# ASCII_05_LMS7002M_RF1.net
KiCad netlist of a schematic drawn in Altium Designer
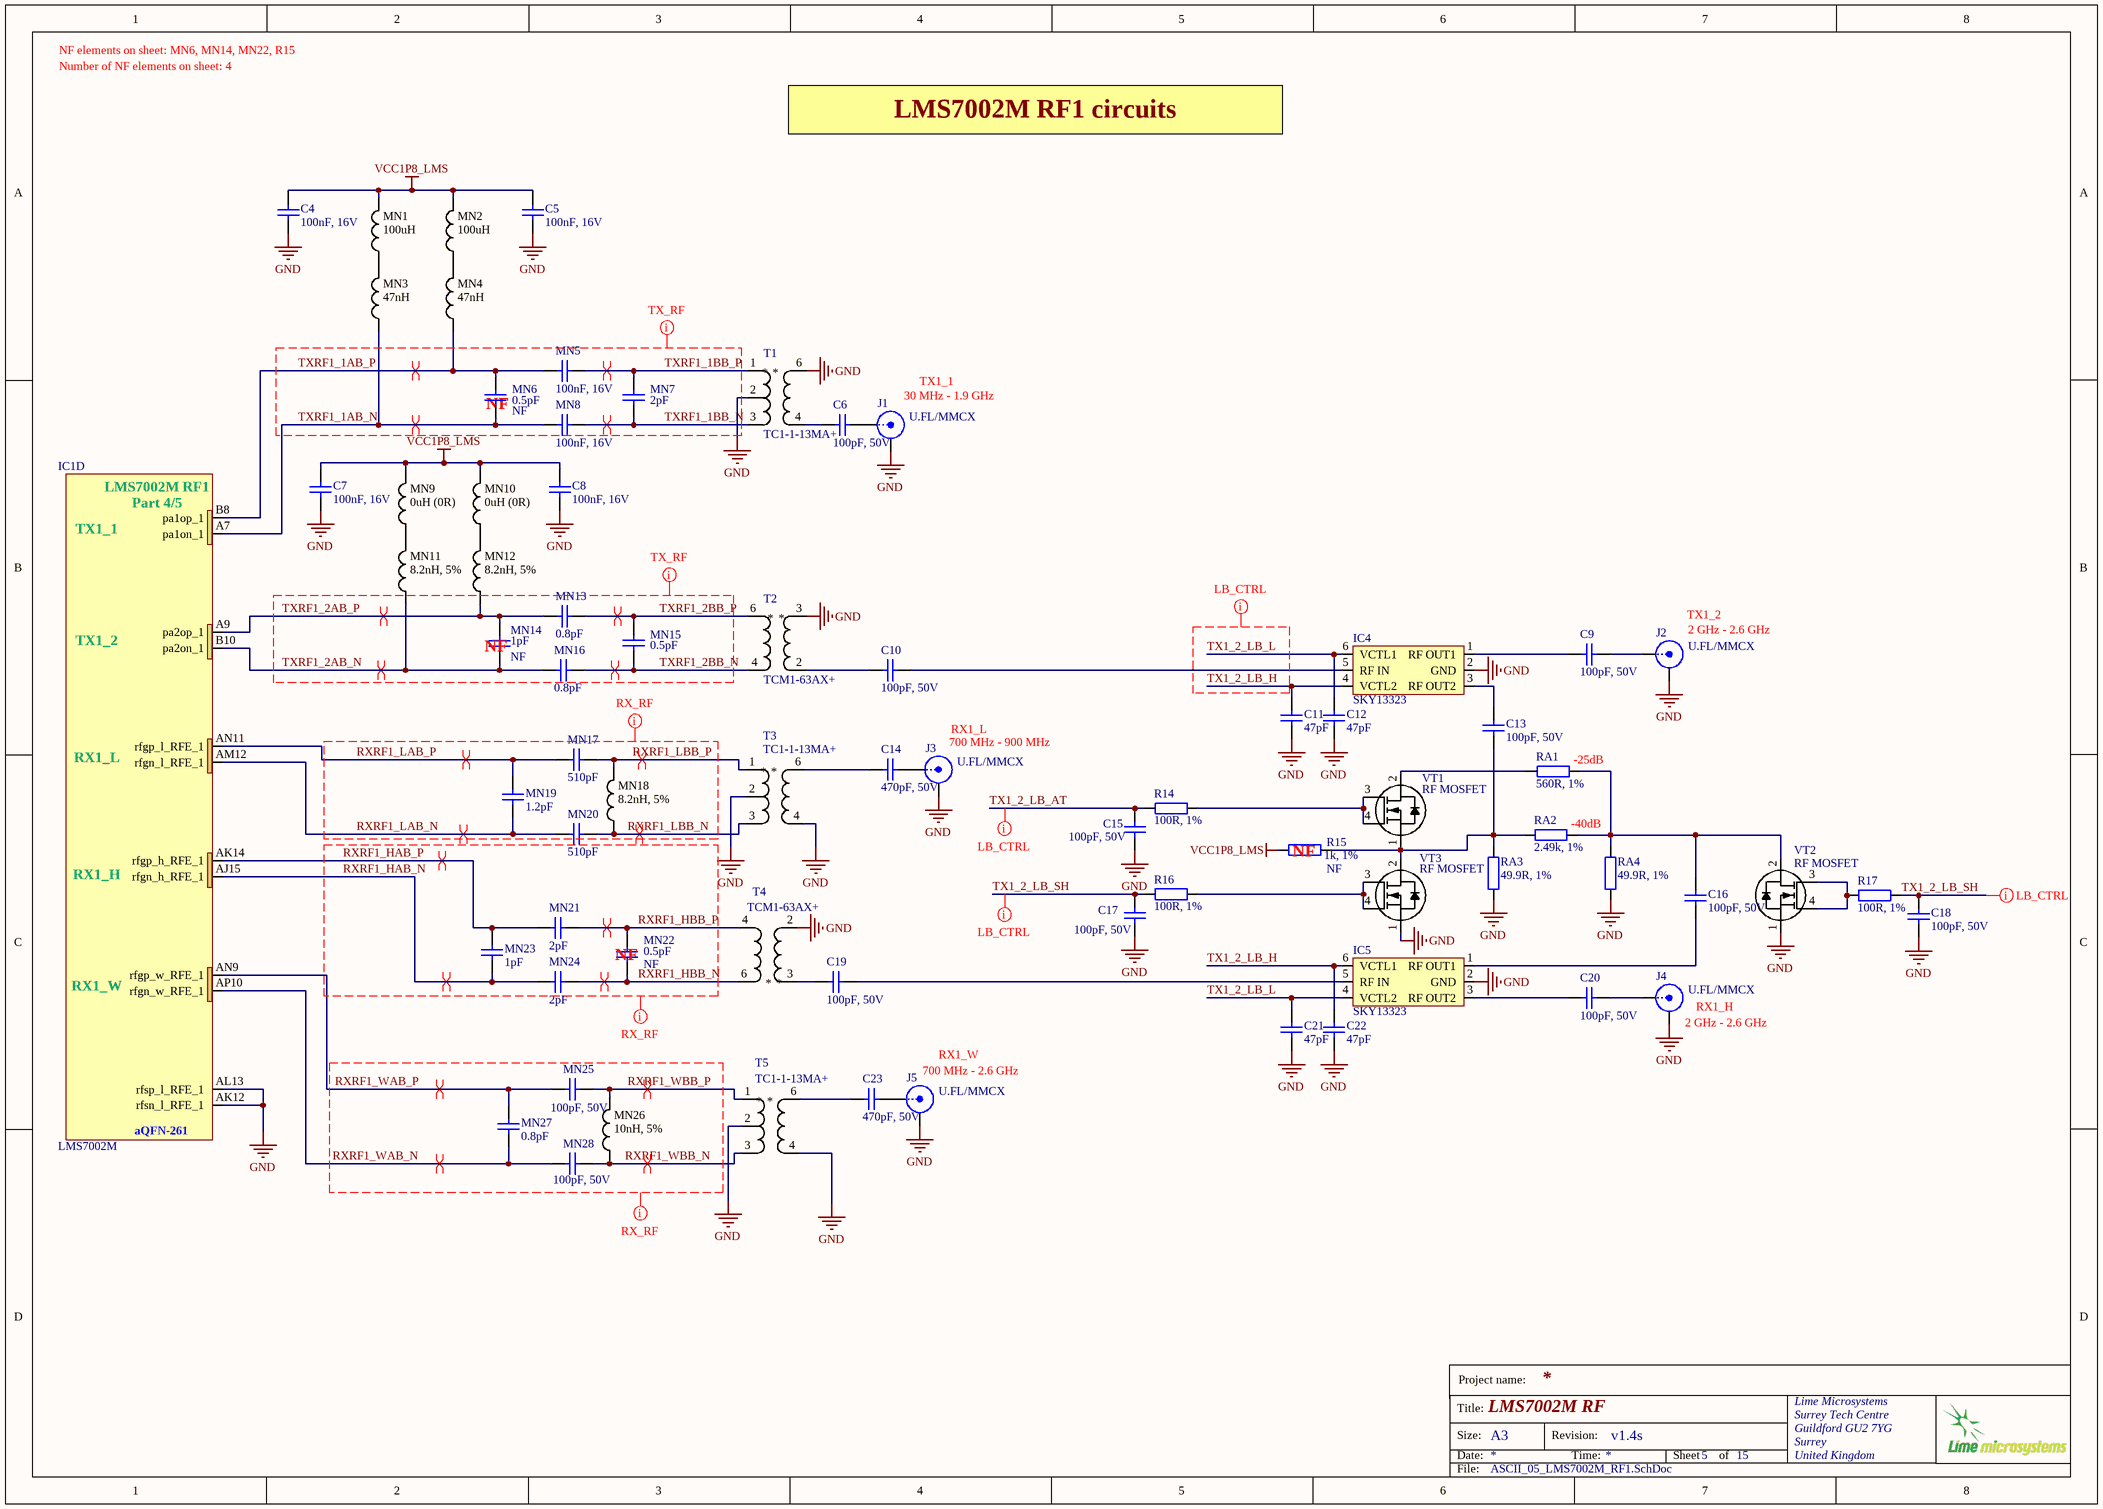
[diagram p0: ASCII_05_LMS7002M_RF1.SchDoc]

(export (version "E")
  (design (tool "Eeschema 10.0.6"))
  (components
    (comp (ref "C4")
      (value "100nF, 16V")
      (footprint "CAP0402")
      (fields
        (field (name "MANUFACTURER") "Murata Electronics")
        (field (name "TOLERANCE") "10 %")
        (field (name "MANUFACTURER PART NUMBER") "GRM155R71C104KA88D")
      )
      (libsource (lib "LimeMicroAltiumLib_schLib") (part "Cap_0402"))
    )
    (comp (ref "C5")
      (value "100nF, 16V")
      (footprint "CAP0402")
      (fields
        (field (name "MANUFACTURER") "Murata Electronics")
        (field (name "TOLERANCE") "10 %")
        (field (name "MANUFACTURER PART NUMBER") "GRM155R71C104KA88D")
      )
      (libsource (lib "LimeMicroAltiumLib_schLib") (part "Cap_0402"))
    )
    (comp (ref "C6")
      (value "100pF, 50V")
      (footprint "CAP0402")
      (fields (field (name "TOLERANCE") "±5%") (field (name "MANUFACTURER") "Yageo"))
      (libsource (lib "LimeMicroAltiumLib_schLib") (part "Cap_0402"))
    )
    (comp (ref "C7")
      (value "100nF, 16V")
      (footprint "CAP0402")
      (fields
        (field (name "MANUFACTURER") "Murata Electronics")
        (field (name "TOLERANCE") "10 %")
        (field (name "MANUFACTURER PART NUMBER") "GRM155R71C104KA88D")
      )
      (libsource (lib "LimeMicroAltiumLib_schLib") (part "Cap_0402"))
    )
    (comp (ref "C8")
      (value "100nF, 16V")
      (footprint "CAP0402")
      (fields
        (field (name "MANUFACTURER") "Murata Electronics")
        (field (name "TOLERANCE") "10 %")
        (field (name "MANUFACTURER PART NUMBER") "GRM155R71C104KA88D")
      )
      (libsource (lib "LimeMicroAltiumLib_schLib") (part "Cap_0402"))
    )
    (comp (ref "C9")
      (value "100pF, 50V")
      (footprint "CAP0402")
      (fields (field (name "TOLERANCE") "±5%") (field (name "MANUFACTURER") "Yageo"))
      (libsource (lib "LimeMicroAltiumLib_schLib") (part "Cap_0402"))
    )
    (comp (ref "C10")
      (value "100pF, 50V")
      (footprint "CAP0402")
      (fields (field (name "TOLERANCE") "±5%") (field (name "MANUFACTURER") "Yageo"))
      (libsource (lib "LimeMicroAltiumLib_schLib") (part "Cap_0402"))
    )
    (comp (ref "C11")
      (value "47pF")
      (footprint "CAP0402")
      (fields (field (name "TOLERANCE") "±1%") (field (name "MANUFACTURER") "TDK Corporation"))
      (libsource (lib "LimeMicroAltiumLib_schLib") (part "Cap_0402"))
    )
    (comp (ref "C12")
      (value "47pF")
      (footprint "CAP0402")
      (fields (field (name "TOLERANCE") "±1%") (field (name "MANUFACTURER") "TDK Corporation"))
      (libsource (lib "LimeMicroAltiumLib_schLib") (part "Cap_0402"))
    )
    (comp (ref "C13")
      (value "100pF, 50V")
      (footprint "CAP0402")
      (fields (field (name "TOLERANCE") "±5%") (field (name "MANUFACTURER") "Yageo"))
      (libsource (lib "LimeMicroAltiumLib_schLib") (part "Cap_0402"))
    )
    (comp (ref "C14")
      (value "470pF, 50V")
      (footprint "CAP0402")
      (fields
        (field (name "MANUFACTURER PART NUMBER") "C1005C0G1H471J050BA")
        (field (name "TOLERANCE") "±5%")
        (field (name "MANUFACTURER") "TDK Corporation")
      )
      (libsource (lib "LimeMicroAltiumLib_schLib") (part "Cap_0402"))
    )
    (comp (ref "C15")
      (value "100pF, 50V")
      (footprint "CAP0402")
      (fields (field (name "TOLERANCE") "±5%") (field (name "MANUFACTURER") "Yageo"))
      (libsource (lib "LimeMicroAltiumLib_schLib") (part "Cap_0402"))
    )
    (comp (ref "C16")
      (value "100pF, 50V")
      (footprint "CAP0402")
      (fields (field (name "TOLERANCE") "±5%") (field (name "MANUFACTURER") "Yageo"))
      (libsource (lib "LimeMicroAltiumLib_schLib") (part "Cap_0402"))
    )
    (comp (ref "C17")
      (value "100pF, 50V")
      (footprint "CAP0402")
      (fields (field (name "TOLERANCE") "±5%") (field (name "MANUFACTURER") "Yageo"))
      (libsource (lib "LimeMicroAltiumLib_schLib") (part "Cap_0402"))
    )
    (comp (ref "C18")
      (value "100pF, 50V")
      (footprint "CAP0402")
      (fields (field (name "TOLERANCE") "±5%") (field (name "MANUFACTURER") "Yageo"))
      (libsource (lib "LimeMicroAltiumLib_schLib") (part "Cap_0402"))
    )
    (comp (ref "C19")
      (value "100pF, 50V")
      (footprint "CAP0402")
      (fields (field (name "TOLERANCE") "±5%") (field (name "MANUFACTURER") "Yageo"))
      (libsource (lib "LimeMicroAltiumLib_schLib") (part "Cap_0402"))
    )
    (comp (ref "C20")
      (value "100pF, 50V")
      (footprint "CAP0402")
      (fields (field (name "TOLERANCE") "±5%") (field (name "MANUFACTURER") "Yageo"))
      (libsource (lib "LimeMicroAltiumLib_schLib") (part "Cap_0402"))
    )
    (comp (ref "C21")
      (value "47pF")
      (footprint "CAP0402")
      (fields (field (name "TOLERANCE") "±1%") (field (name "MANUFACTURER") "TDK Corporation"))
      (libsource (lib "LimeMicroAltiumLib_schLib") (part "Cap_0402"))
    )
    (comp (ref "C22")
      (value "47pF")
      (footprint "CAP0402")
      (fields (field (name "TOLERANCE") "±1%") (field (name "MANUFACTURER") "TDK Corporation"))
      (libsource (lib "LimeMicroAltiumLib_schLib") (part "Cap_0402"))
    )
    (comp (ref "C23")
      (value "470pF, 50V")
      (footprint "CAP0402")
      (fields
        (field (name "MANUFACTURER PART NUMBER") "C1005C0G1H471J050BA")
        (field (name "TOLERANCE") "±5%")
        (field (name "MANUFACTURER") "TDK Corporation")
      )
      (libsource (lib "LimeMicroAltiumLib_schLib") (part "Cap_0402"))
    )
    (comp (ref "IC1")
      (value "LMS7002M")
      (footprint "LMS7002M_v3")
      (fields (field (name "MANUFACTURER") "Lime Microsystems"))
      (libsource (lib "LimeMicroAltiumLib_schLib") (part "LMS7002M"))
    )
    (comp (ref "IC4")
      (value "SKY13323")
      (footprint "SKY13323-378LF")
      (description "SKY13323-378LF: 0.1-3.0 GHz GaAs SPDT Switch")
      (fields (field (name "MANUFACTURER") "Skyworks Solutions Inc."))
      (libsource (lib "LimeMicroAltiumLib_schLib") (part "SKY13323"))
    )
    (comp (ref "IC5")
      (value "SKY13323")
      (footprint "SKY13323-378LF")
      (description "SKY13323-378LF: 0.1-3.0 GHz GaAs SPDT Switch")
      (fields (field (name "MANUFACTURER") "Skyworks Solutions Inc."))
      (libsource (lib "LimeMicroAltiumLib_schLib") (part "SKY13323"))
    )
    (comp (ref "J1")
      (value "U.FL/MMCX")
      (footprint "MMCX_UFL_conn_u")
      (description "CONN UMC RCPT STR 50 OHM SMD")
      (fields (field (name "MANUFACTURER") "Molex, LLC"))
      (libsource (lib "LimeMicroAltiumLib_schLib") (part "RF_IF_connector"))
    )
    (comp (ref "J2")
      (value "U.FL/MMCX")
      (footprint "MMCX_UFL_conn_u")
      (description "CONN UMC RCPT STR 50 OHM SMD")
      (fields (field (name "MANUFACTURER") "Molex, LLC"))
      (libsource (lib "LimeMicroAltiumLib_schLib") (part "RF_IF_connector"))
    )
    (comp (ref "J3")
      (value "U.FL/MMCX")
      (footprint "MMCX_UFL_conn_u")
      (description "CONN UMC RCPT STR 50 OHM SMD")
      (fields (field (name "MANUFACTURER") "Molex, LLC"))
      (libsource (lib "LimeMicroAltiumLib_schLib") (part "RF_IF_connector"))
    )
    (comp (ref "J4")
      (value "U.FL/MMCX")
      (footprint "MMCX_UFL_conn_u")
      (description "CONN UMC RCPT STR 50 OHM SMD")
      (fields (field (name "MANUFACTURER") "Molex, LLC"))
      (libsource (lib "LimeMicroAltiumLib_schLib") (part "RF_IF_connector"))
    )
    (comp (ref "J5")
      (value "U.FL/MMCX")
      (footprint "MMCX_UFL_conn_u")
      (description "CONN UMC RCPT STR 50 OHM SMD")
      (fields (field (name "MANUFACTURER") "Molex, LLC"))
      (libsource (lib "LimeMicroAltiumLib_schLib") (part "RF_IF_connector"))
    )
    (comp (ref "MN1")
      (value "100uH")
      (footprint "RES0805")
      (fields
        (field (name "TOLERANCE") "±10%")
        (field (name "MANUFACTURER") "TDK Corporation")
        (field (name "MANUFACTURER PART NUMBER") "MLF2012C101KT000")
      )
      (libsource (lib "LimeMicroAltiumLib_schLib") (part "Inductor_0603"))
    )
    (comp (ref "MN2")
      (value "100uH")
      (footprint "RES0805")
      (fields
        (field (name "TOLERANCE") "±10%")
        (field (name "MANUFACTURER") "TDK Corporation")
        (field (name "MANUFACTURER PART NUMBER") "MLF2012C101KT000")
      )
      (libsource (lib "LimeMicroAltiumLib_schLib") (part "Inductor_0603"))
    )
    (comp (ref "MN3")
      (value "47nH")
      (footprint "RES0402")
      (fields
        (field (name "MANUFACTURER") "COILCRAFT")
        (field (name "MANUFACTURER PART NUMBER") "0402HP-47NXJLU")
      )
      (libsource (lib "LimeMicroAltiumLib_schLib") (part "Inductor_0603"))
    )
    (comp (ref "MN4")
      (value "47nH")
      (footprint "RES0402")
      (fields
        (field (name "MANUFACTURER") "COILCRAFT")
        (field (name "MANUFACTURER PART NUMBER") "0402HP-47NXJLU")
      )
      (libsource (lib "LimeMicroAltiumLib_schLib") (part "Inductor_0603"))
    )
    (comp (ref "MN5")
      (value "100nF, 16V")
      (footprint "CAP0402")
      (fields
        (field (name "MANUFACTURER") "Murata Electronics")
        (field (name "TOLERANCE") "10 %")
        (field (name "MANUFACTURER PART NUMBER") "GRM155R71C104KA88D")
      )
      (libsource (lib "LimeMicroAltiumLib_schLib") (part "Cap_0402"))
    )
    (comp (ref "MN6")
      (value "0.5pF")
      (footprint "CAP0402")
      (fields
        (field (name "ASSEMBLY INFO") "NF")
        (field (name "TOLERANCE") "±0.25pF")
        (field (name "MANUFACTURER") "Yageo")
      )
      (libsource (lib "LimeMicroAltiumLib_schLib") (part "Cap_0402"))
    )
    (comp (ref "MN7")
      (value "2pF")
      (footprint "CAP0402")
      (fields (field (name "MANUFACTURER PART NUMBER") "04025U2R0BAT2A") (field (name "MANUFACTURER") "AVX"))
      (libsource (lib "LimeMicroAltiumLib_schLib") (part "Cap_0402"))
    )
    (comp (ref "MN8")
      (value "100nF, 16V")
      (footprint "CAP0402")
      (fields
        (field (name "MANUFACTURER") "Murata Electronics")
        (field (name "TOLERANCE") "10 %")
        (field (name "MANUFACTURER PART NUMBER") "GRM155R71C104KA88D")
      )
      (libsource (lib "LimeMicroAltiumLib_schLib") (part "Cap_0402"))
    )
    (comp (ref "MN9")
      (value "0uH (0R)")
      (footprint "RES0805")
      (fields (field (name "MANUFACTURER") "BOURNS"))
      (libsource (lib "LimeMicroAltiumLib_schLib") (part "Inductor_0603"))
    )
    (comp (ref "MN10")
      (value "0uH (0R)")
      (footprint "RES0805")
      (fields (field (name "MANUFACTURER") "BOURNS"))
      (libsource (lib "LimeMicroAltiumLib_schLib") (part "Inductor_0603"))
    )
    (comp (ref "MN11")
      (value "8.2nH, 5%")
      (footprint "RES0402")
      (fields (field (name "MANUFACTURER") "COILCRAFT"))
      (libsource (lib "LimeMicroAltiumLib_schLib") (part "Inductor_0603"))
    )
    (comp (ref "MN12")
      (value "8.2nH, 5%")
      (footprint "RES0402")
      (fields (field (name "MANUFACTURER") "COILCRAFT"))
      (libsource (lib "LimeMicroAltiumLib_schLib") (part "Inductor_0603"))
    )
    (comp (ref "MN13")
      (value "0.8pF")
      (footprint "CAP0402")
      (fields
        (field (name "TOLERANCE") "±0.1pF")
        (field (name "MANUFACTURER") "Murata Electronics North America")
        (field (name "MANUFACTURER PART NUMBER") "GRM1555C1HR80BA01D")
      )
      (libsource (lib "LimeMicroAltiumLib_schLib") (part "Cap_0402"))
    )
    (comp (ref "MN14")
      (value "1pF")
      (footprint "CAP0402")
      (fields
        (field (name "ASSEMBLY INFO") "NF")
        (field (name "MANUFACTURER") "TDK Corporation")
        (field (name "TOLERANCE") "±0.1pF")
      )
      (libsource (lib "LimeMicroAltiumLib_schLib") (part "Cap_0402"))
    )
    (comp (ref "MN15")
      (value "0.5pF")
      (footprint "CAP0402")
      (fields (field (name "TOLERANCE") "±0.25pF") (field (name "MANUFACTURER") "Yageo"))
      (libsource (lib "LimeMicroAltiumLib_schLib") (part "Cap_0402"))
    )
    (comp (ref "MN16")
      (value "0.8pF")
      (footprint "CAP0402")
      (fields
        (field (name "TOLERANCE") "±0.1pF")
        (field (name "MANUFACTURER") "Murata Electronics North America")
        (field (name "MANUFACTURER PART NUMBER") "GRM1555C1HR80BA01D")
      )
      (libsource (lib "LimeMicroAltiumLib_schLib") (part "Cap_0402"))
    )
    (comp (ref "MN17")
      (value "510pF")
      (footprint "CAP0402")
      (fields
        (field (name "TOLERANCE") "±5%")
        (field (name "MANUFACTURER") "Murata Electronics North America")
        (field (name "MANUFACTURER PART NUMBER") "GRM1555C1H511JA01D")
      )
      (libsource (lib "LimeMicroAltiumLib_schLib") (part "Cap_0402"))
    )
    (comp (ref "MN18")
      (value "8.2nH, 5%")
      (footprint "RES0402")
      (fields (field (name "MANUFACTURER") "COILCRAFT"))
      (libsource (lib "LimeMicroAltiumLib_schLib") (part "Inductor_0603"))
    )
    (comp (ref "MN19")
      (value "1.2pF")
      (footprint "CAP0402")
      (fields
        (field (name "MANUFACTURER") "Murata Electronics North America")
        (field (name "MANUFACTURER PART NUMBER") "GRM1555C1H1R2CA01D")
        (field (name "TOLERANCE") "±0.25pF")
      )
      (libsource (lib "LimeMicroAltiumLib_schLib") (part "Cap_0402"))
    )
    (comp (ref "MN20")
      (value "510pF")
      (footprint "CAP0402")
      (fields
        (field (name "TOLERANCE") "±5%")
        (field (name "MANUFACTURER") "Murata Electronics North America")
        (field (name "MANUFACTURER PART NUMBER") "GRM1555C1H511JA01D")
      )
      (libsource (lib "LimeMicroAltiumLib_schLib") (part "Cap_0402"))
    )
    (comp (ref "MN21")
      (value "2pF")
      (footprint "CAP0402")
      (fields (field (name "MANUFACTURER PART NUMBER") "04025U2R0BAT2A") (field (name "MANUFACTURER") "AVX"))
      (libsource (lib "LimeMicroAltiumLib_schLib") (part "Cap_0402"))
    )
    (comp (ref "MN22")
      (value "0.5pF")
      (footprint "CAP0402")
      (fields
        (field (name "ASSEMBLY INFO") "NF")
        (field (name "TOLERANCE") "±0.25pF")
        (field (name "MANUFACTURER") "Yageo")
      )
      (libsource (lib "LimeMicroAltiumLib_schLib") (part "Cap_0402"))
    )
    (comp (ref "MN23")
      (value "1pF")
      (footprint "CAP0402")
      (fields (field (name "MANUFACTURER") "TDK Corporation") (field (name "TOLERANCE") "±0.1pF"))
      (libsource (lib "LimeMicroAltiumLib_schLib") (part "Cap_0402"))
    )
    (comp (ref "MN24")
      (value "2pF")
      (footprint "CAP0402")
      (fields (field (name "MANUFACTURER PART NUMBER") "04025U2R0BAT2A") (field (name "MANUFACTURER") "AVX"))
      (libsource (lib "LimeMicroAltiumLib_schLib") (part "Cap_0402"))
    )
    (comp (ref "MN25")
      (value "100pF, 50V")
      (footprint "CAP0402")
      (fields (field (name "TOLERANCE") "±5%") (field (name "MANUFACTURER") "Yageo"))
      (libsource (lib "LimeMicroAltiumLib_schLib") (part "Cap_0402"))
    )
    (comp (ref "MN26")
      (value "10nH, 5%")
      (footprint "RES0402")
      (fields (field (name "MANUFACTURER") "COILCRAFT"))
      (libsource (lib "LimeMicroAltiumLib_schLib") (part "Inductor_0603"))
    )
    (comp (ref "MN27")
      (value "0.8pF")
      (footprint "CAP0402")
      (fields
        (field (name "TOLERANCE") "±0.1pF")
        (field (name "MANUFACTURER") "Murata Electronics North America")
        (field (name "MANUFACTURER PART NUMBER") "GRM1555C1HR80BA01D")
      )
      (libsource (lib "LimeMicroAltiumLib_schLib") (part "Cap_0402"))
    )
    (comp (ref "MN28")
      (value "100pF, 50V")
      (footprint "CAP0402")
      (fields (field (name "TOLERANCE") "±5%") (field (name "MANUFACTURER") "Yageo"))
      (libsource (lib "LimeMicroAltiumLib_schLib") (part "Cap_0402"))
    )
    (comp (ref "R14")
      (value "100R, 1%")
      (footprint "RES0402")
      (fields (field (name "TOLERANCE") "±1%") (field (name "MANUFACTURER") "Stackpole Electronics Inc."))
      (libsource (lib "LimeFPGAboard_schLib") (part "Res_0402"))
    )
    (comp (ref "R15")
      (value "1k, 1%")
      (footprint "RES0402")
      (fields
        (field (name "ASSEMBLY INFO") "NF")
        (field (name "MANUFACTURER") "Stackpole Electronics Inc")
        (field (name "TOLERANCE") "±1%")
      )
      (libsource (lib "LimeMicroAltiumLib_schLib") (part "Res_0402"))
    )
    (comp (ref "R16")
      (value "100R, 1%")
      (footprint "RES0402")
      (fields (field (name "TOLERANCE") "±1%") (field (name "MANUFACTURER") "Stackpole Electronics Inc."))
      (libsource (lib "LimeFPGAboard_schLib") (part "Res_0402"))
    )
    (comp (ref "R17")
      (value "100R, 1%")
      (footprint "RES0402")
      (fields (field (name "TOLERANCE") "±1%") (field (name "MANUFACTURER") "Stackpole Electronics Inc."))
      (libsource (lib "LimeFPGAboard_schLib") (part "Res_0402"))
    )
    (comp (ref "RA1")
      (value "560R, 1%")
      (footprint "RES0402")
      (fields
        (field (name "MANUFACTURER PART NUMBER") "CRCW0402560RFKED")
        (field (name "TOLERANCE") "±1%")
        (field (name "MANUFACTURER") "Vishay Dale")
      )
      (libsource (lib "LimeMicroAltiumLib_schLib") (part "Res_0402"))
    )
    (comp (ref "RA2")
      (value "2.49k, 1%")
      (footprint "RES0402")
      (fields
        (field (name "TOLERANCE") "±1%")
        (field (name "MANUFACTURER PART NUMBER") "RC0402FR-072K49L")
        (field (name "MANUFACTURER") "Yageo")
      )
      (libsource (lib "LimeMicroAltiumLib_schLib") (part "Res_0402"))
    )
    (comp (ref "RA3")
      (value "49.9R, 1%")
      (footprint "RES0402")
      (fields
        (field (name "TOLERANCE") "±1%")
        (field (name "MANUFACTURER") "Samsung Electro-Mechanics America, Inc.")
        (field (name "MANUFACTURER PART NUMBER") "RC1005F49R9CS")
      )
      (libsource (lib "LimeMicroAltiumLib_schLib") (part "Res_0402"))
    )
    (comp (ref "RA4")
      (value "49.9R, 1%")
      (footprint "RES0402")
      (fields
        (field (name "TOLERANCE") "±1%")
        (field (name "MANUFACTURER") "Samsung Electro-Mechanics America, Inc.")
        (field (name "MANUFACTURER PART NUMBER") "RC1005F49R9CS")
      )
      (libsource (lib "LimeMicroAltiumLib_schLib") (part "Res_0402"))
    )
    (comp (ref "T1")
      (value "TC1-1-13MA+")
      (footprint "TC1-1-13MA+_v2")
      (fields (field (name "MANUFACTURER") "Mini-Circuits"))
      (libsource (lib "LimeMicroAltiumLib_schLib") (part "Balun"))
    )
    (comp (ref "T2")
      (value "TCM1-63AX+")
      (footprint "TCM1-63AX+_v2")
      (fields (field (name "MANUFACTURER") "Mini-circuits"))
      (libsource (lib "LimeMicroAltiumLib_schLib") (part "Balun_v2"))
    )
    (comp (ref "T3")
      (value "TC1-1-13MA+")
      (footprint "TC1-1-13MA+_v2")
      (fields (field (name "MANUFACTURER") "Mini-Circuits"))
      (libsource (lib "LimeMicroAltiumLib_schLib") (part "Balun"))
    )
    (comp (ref "T4")
      (value "TCM1-63AX+")
      (footprint "TCM1-63AX+_v2")
      (fields (field (name "MANUFACTURER") "Mini-circuits"))
      (libsource (lib "") (part "Balun_v2_1"))
    )
    (comp (ref "T5")
      (value "TC1-1-13MA+")
      (footprint "TC1-1-13MA+_v2")
      (fields (field (name "MANUFACTURER") "Mini-Circuits"))
      (libsource (lib "LimeMicroAltiumLib_schLib") (part "Balun"))
    )
    (comp (ref "VT1")
      (value "RF MOSFET")
      (footprint "BF1105R_SOT143R4")
      (fields (field (name "MANUFACTURER") "NXP Semiconductors"))
      (libsource (lib "LimeMicroAltiumLib_schLib") (part "BF1105R,215"))
    )
    (comp (ref "VT2")
      (value "RF MOSFET")
      (footprint "BF1105R_SOT143R4")
      (fields (field (name "MANUFACTURER") "NXP Semiconductors"))
      (libsource (lib "LimeMicroAltiumLib_schLib") (part "BF1105R,215"))
    )
    (comp (ref "VT3")
      (value "RF MOSFET")
      (footprint "BF1105R_SOT143R4")
      (fields (field (name "MANUFACTURER") "NXP Semiconductors"))
      (libsource (lib "LimeMicroAltiumLib_schLib") (part "BF1105R,215"))
    )
  )
  (nets
    (net (code "1") (name "/RXRF1_HAB_N") (class "Default")
      (node (ref "IC1") (pin "AJ15") (pinfunction "rfgn_h_RFE_1_AJ15") (pintype "passive"))
      (node (ref "MN23") (pin "1") (pinfunction "1_1") (pintype "passive"))
      (node (ref "MN24") (pin "2") (pinfunction "2_2") (pintype "passive"))
    )
    (net (code "2") (name "/RXRF1_HAB_P") (class "Default")
      (node (ref "IC1") (pin "AK14") (pinfunction "rfgp_h_RFE_1_AK14") (pintype "passive"))
      (node (ref "MN21") (pin "2") (pinfunction "2_2") (pintype "passive"))
      (node (ref "MN23") (pin "2") (pinfunction "2_2") (pintype "passive"))
    )
    (net (code "3") (name "/RXRF1_HBB_N") (class "Default")
      (node (ref "MN22") (pin "1") (pinfunction "1_1") (pintype "passive"))
      (node (ref "MN24") (pin "1") (pinfunction "1_1") (pintype "passive"))
      (node (ref "T4") (pin "6") (pinfunction "6_6") (pintype "passive"))
    )
    (net (code "4") (name "/RXRF1_HBB_P") (class "Default")
      (node (ref "MN21") (pin "1") (pinfunction "1_1") (pintype "passive"))
      (node (ref "MN22") (pin "2") (pinfunction "2_2") (pintype "passive"))
      (node (ref "T4") (pin "4") (pinfunction "4_4") (pintype "passive"))
    )
    (net (code "5") (name "/RXRF1_LAB_N") (class "Default")
      (node (ref "IC1") (pin "AM12") (pinfunction "rfgn_l_RFE_1_AM12") (pintype "passive"))
      (node (ref "MN19") (pin "1") (pinfunction "1_1") (pintype "passive"))
      (node (ref "MN20") (pin "2") (pinfunction "2_2") (pintype "passive"))
    )
    (net (code "6") (name "/RXRF1_LAB_P") (class "Default")
      (node (ref "IC1") (pin "AN11") (pinfunction "rfgp_l_RFE_1_AN11") (pintype "passive"))
      (node (ref "MN17") (pin "2") (pinfunction "2_2") (pintype "passive"))
      (node (ref "MN19") (pin "2") (pinfunction "2_2") (pintype "passive"))
    )
    (net (code "7") (name "/RXRF1_LBB_N") (class "Default")
      (node (ref "MN18") (pin "1") (pinfunction "1_1") (pintype "passive"))
      (node (ref "MN20") (pin "1") (pinfunction "1_1") (pintype "passive"))
      (node (ref "T3") (pin "3") (pinfunction "3_3") (pintype "passive"))
    )
    (net (code "8") (name "/RXRF1_LBB_P") (class "Default")
      (node (ref "MN17") (pin "1") (pinfunction "1_1") (pintype "passive"))
      (node (ref "MN18") (pin "2") (pinfunction "2_2") (pintype "passive"))
      (node (ref "T3") (pin "1") (pinfunction "1_1") (pintype "passive"))
    )
    (net (code "9") (name "/RXRF1_WAB_N") (class "Default")
      (node (ref "IC1") (pin "AP10") (pinfunction "rfgn_w_RFE_1_AP10") (pintype "passive"))
      (node (ref "MN27") (pin "2") (pinfunction "2_2") (pintype "passive"))
      (node (ref "MN28") (pin "2") (pinfunction "2_2") (pintype "passive"))
    )
    (net (code "10") (name "/RXRF1_WAB_P") (class "Default")
      (node (ref "IC1") (pin "AN9") (pinfunction "rfgp_w_RFE_1_AN9") (pintype "passive"))
      (node (ref "MN25") (pin "2") (pinfunction "2_2") (pintype "passive"))
      (node (ref "MN27") (pin "1") (pinfunction "1_1") (pintype "passive"))
    )
    (net (code "11") (name "/RXRF1_WBB_N") (class "Default")
      (node (ref "MN26") (pin "1") (pinfunction "1_1") (pintype "passive"))
      (node (ref "MN28") (pin "1") (pinfunction "1_1") (pintype "passive"))
      (node (ref "T5") (pin "3") (pinfunction "3_3") (pintype "passive"))
    )
    (net (code "12") (name "/RXRF1_WBB_P") (class "Default")
      (node (ref "MN25") (pin "1") (pinfunction "1_1") (pintype "passive"))
      (node (ref "MN26") (pin "2") (pinfunction "2_2") (pintype "passive"))
      (node (ref "T5") (pin "1") (pinfunction "1_1") (pintype "passive"))
    )
    (net (code "13") (name "/TX1_2_LB_AT") (class "Default")
      (node (ref "C15") (pin "1") (pinfunction "1_1") (pintype "passive"))
      (node (ref "R14") (pin "2") (pinfunction "2_2") (pintype "passive"))
    )
    (net (code "14") (name "/TX1_2_LB_H") (class "Default")
      (node (ref "C11") (pin "2") (pinfunction "2_2") (pintype "passive"))
      (node (ref "C22") (pin "2") (pinfunction "2_2") (pintype "passive"))
      (node (ref "IC4") (pin "4") (pinfunction "VCTL2_4") (pintype "input"))
      (node (ref "IC5") (pin "6") (pinfunction "VCTL1_6") (pintype "input"))
    )
    (net (code "15") (name "/TX1_2_LB_L") (class "Default")
      (node (ref "C12") (pin "2") (pinfunction "2_2") (pintype "passive"))
      (node (ref "C21") (pin "2") (pinfunction "2_2") (pintype "passive"))
      (node (ref "IC4") (pin "6") (pinfunction "VCTL1_6") (pintype "input"))
      (node (ref "IC5") (pin "4") (pinfunction "VCTL2_4") (pintype "input"))
    )
    (net (code "16") (name "/TX1_2_LB_SH") (class "Default")
      (node (ref "C17") (pin "1") (pinfunction "1_1") (pintype "passive"))
      (node (ref "C18") (pin "1") (pinfunction "1_1") (pintype "passive"))
      (node (ref "R16") (pin "2") (pinfunction "2_2") (pintype "passive"))
      (node (ref "R17") (pin "1") (pinfunction "1_1") (pintype "passive"))
    )
    (net (code "17") (name "/TXRF1_1AB_N") (class "Default")
      (node (ref "IC1") (pin "A7") (pinfunction "pa1on_1_A7") (pintype "passive"))
      (node (ref "MN3") (pin "1") (pinfunction "1_1") (pintype "passive"))
      (node (ref "MN6") (pin "1") (pinfunction "1_1") (pintype "passive"))
      (node (ref "MN8") (pin "1") (pinfunction "1_1") (pintype "passive"))
    )
    (net (code "18") (name "/TXRF1_1AB_P") (class "Default")
      (node (ref "IC1") (pin "B8") (pinfunction "pa1op_1_B8") (pintype "passive"))
      (node (ref "MN4") (pin "1") (pinfunction "1_1") (pintype "passive"))
      (node (ref "MN5") (pin "2") (pinfunction "2_2") (pintype "passive"))
      (node (ref "MN6") (pin "2") (pinfunction "2_2") (pintype "passive"))
    )
    (net (code "19") (name "/TXRF1_1BB_N") (class "Default")
      (node (ref "MN7") (pin "1") (pinfunction "1_1") (pintype "passive"))
      (node (ref "MN8") (pin "2") (pinfunction "2_2") (pintype "passive"))
      (node (ref "T1") (pin "3") (pinfunction "3_3") (pintype "passive"))
    )
    (net (code "20") (name "/TXRF1_1BB_P") (class "Default")
      (node (ref "MN5") (pin "1") (pinfunction "1_1") (pintype "passive"))
      (node (ref "MN7") (pin "2") (pinfunction "2_2") (pintype "passive"))
      (node (ref "T1") (pin "1") (pinfunction "1_1") (pintype "passive"))
    )
    (net (code "21") (name "/TXRF1_2AB_N") (class "Default")
      (node (ref "IC1") (pin "B10") (pinfunction "pa2on_1_B10") (pintype "passive"))
      (node (ref "MN11") (pin "1") (pinfunction "1_1") (pintype "passive"))
      (node (ref "MN14") (pin "2") (pinfunction "2_2") (pintype "passive"))
      (node (ref "MN16") (pin "2") (pinfunction "2_2") (pintype "passive"))
    )
    (net (code "22") (name "/TXRF1_2AB_P") (class "Default")
      (node (ref "IC1") (pin "A9") (pinfunction "pa2op_1_A9") (pintype "passive"))
      (node (ref "MN12") (pin "1") (pinfunction "1_1") (pintype "passive"))
      (node (ref "MN13") (pin "2") (pinfunction "2_2") (pintype "passive"))
      (node (ref "MN14") (pin "1") (pinfunction "1_1") (pintype "passive"))
    )
    (net (code "23") (name "/TXRF1_2BB_N") (class "Default")
      (node (ref "MN15") (pin "1") (pinfunction "1_1") (pintype "passive"))
      (node (ref "MN16") (pin "1") (pinfunction "1_1") (pintype "passive"))
      (node (ref "T2") (pin "4") (pinfunction "4_4") (pintype "passive"))
    )
    (net (code "24") (name "/TXRF1_2BB_P") (class "Default")
      (node (ref "MN13") (pin "1") (pinfunction "1_1") (pintype "passive"))
      (node (ref "MN15") (pin "2") (pinfunction "2_2") (pintype "passive"))
      (node (ref "T2") (pin "6") (pinfunction "6_6") (pintype "passive"))
    )
    (net (code "25") (name "GND") (class "Default")
      (node (ref "C11") (pin "1") (pinfunction "1_1") (pintype "passive"))
      (node (ref "C12") (pin "1") (pinfunction "1_1") (pintype "passive"))
      (node (ref "C15") (pin "2") (pinfunction "2_2") (pintype "passive"))
      (node (ref "C17") (pin "2") (pinfunction "2_2") (pintype "passive"))
      (node (ref "C18") (pin "2") (pinfunction "2_2") (pintype "passive"))
      (node (ref "C21") (pin "1") (pinfunction "1_1") (pintype "passive"))
      (node (ref "C22") (pin "1") (pinfunction "1_1") (pintype "passive"))
      (node (ref "C4") (pin "1") (pinfunction "1_1") (pintype "passive"))
      (node (ref "C5") (pin "1") (pinfunction "1_1") (pintype "passive"))
      (node (ref "C7") (pin "1") (pinfunction "1_1") (pintype "passive"))
      (node (ref "C8") (pin "1") (pinfunction "1_1") (pintype "passive"))
      (node (ref "IC1") (pin "AK12") (pinfunction "rfsn_l_RFE_1_AK12") (pintype "passive"))
      (node (ref "IC1") (pin "AL13") (pinfunction "rfsp_l_RFE_1_AL13") (pintype "passive"))
      (node (ref "IC4") (pin "2") (pinfunction "GND_2") (pintype "passive"))
      (node (ref "IC5") (pin "2") (pinfunction "GND_2") (pintype "passive"))
      (node (ref "J1") (pin "2") (pinfunction "Y_2") (pintype "passive"))
      (node (ref "J2") (pin "2") (pinfunction "Y_2") (pintype "passive"))
      (node (ref "J3") (pin "2") (pinfunction "Y_2") (pintype "passive"))
      (node (ref "J4") (pin "2") (pinfunction "Y_2") (pintype "passive"))
      (node (ref "J5") (pin "2") (pinfunction "Y_2") (pintype "passive"))
      (node (ref "RA3") (pin "1") (pinfunction "1_1") (pintype "passive"))
      (node (ref "RA4") (pin "1") (pinfunction "1_1") (pintype "passive"))
      (node (ref "T1") (pin "2") (pinfunction "2_2") (pintype "passive"))
      (node (ref "T1") (pin "6") (pinfunction "6_6") (pintype "passive"))
      (node (ref "T2") (pin "3") (pinfunction "3_3") (pintype "passive"))
      (node (ref "T3") (pin "2") (pinfunction "2_2") (pintype "passive"))
      (node (ref "T3") (pin "4") (pinfunction "4_4") (pintype "passive"))
      (node (ref "T4") (pin "2") (pinfunction "2_2") (pintype "passive"))
      (node (ref "T5") (pin "2") (pinfunction "2_2") (pintype "passive"))
      (node (ref "T5") (pin "4") (pinfunction "4_4") (pintype "passive"))
      (node (ref "VT2") (pin "1") (pinfunction "S_1") (pintype "passive"))
      (node (ref "VT3") (pin "1") (pinfunction "S_1") (pintype "passive"))
    )
    (net (code "26") (name "Net-(C6-Pad2)") (class "Default")
      (node (ref "C6") (pin "2") (pinfunction "2_2") (pintype "passive"))
      (node (ref "T1") (pin "4") (pinfunction "4_4") (pintype "passive"))
    )
    (net (code "27") (name "Net-(C10-Pad2)") (class "Default")
      (node (ref "C10") (pin "2") (pinfunction "2_2") (pintype "passive"))
      (node (ref "T2") (pin "2") (pinfunction "2_2") (pintype "passive"))
    )
    (net (code "28") (name "Net-(C14-Pad2)") (class "Default")
      (node (ref "C14") (pin "2") (pinfunction "2_2") (pintype "passive"))
      (node (ref "T3") (pin "6") (pinfunction "6_6") (pintype "passive"))
    )
    (net (code "29") (name "Net-(C19-Pad2)") (class "Default")
      (node (ref "C19") (pin "2") (pinfunction "2_2") (pintype "passive"))
      (node (ref "T4") (pin "3") (pinfunction "3_3") (pintype "passive"))
    )
    (net (code "30") (name "Net-(C23-Pad2)") (class "Default")
      (node (ref "C23") (pin "2") (pinfunction "2_2") (pintype "passive"))
      (node (ref "T5") (pin "6") (pinfunction "6_6") (pintype "passive"))
    )
    (net (code "31") (name "Net-(IC4-RF_IN)") (class "Default")
      (node (ref "C10") (pin "1") (pinfunction "1_1") (pintype "passive"))
      (node (ref "IC4") (pin "5") (pinfunction "RF_IN_5") (pintype "input"))
    )
    (net (code "32") (name "Net-(IC4-RF_OUT1)") (class "Default")
      (node (ref "C9") (pin "2") (pinfunction "2_2") (pintype "passive"))
      (node (ref "IC4") (pin "1") (pinfunction "RF_OUT1_1") (pintype "output"))
    )
    (net (code "33") (name "Net-(IC4-RF_OUT2)") (class "Default")
      (node (ref "C13") (pin "1") (pinfunction "1_1") (pintype "passive"))
      (node (ref "IC4") (pin "3") (pinfunction "RF_OUT2_3") (pintype "output"))
    )
    (net (code "34") (name "Net-(IC5-RF_IN)") (class "Default")
      (node (ref "C19") (pin "1") (pinfunction "1_1") (pintype "passive"))
      (node (ref "IC5") (pin "5") (pinfunction "RF_IN_5") (pintype "input"))
    )
    (net (code "35") (name "Net-(IC5-RF_OUT1)") (class "Default")
      (node (ref "C16") (pin "2") (pinfunction "2_2") (pintype "passive"))
      (node (ref "IC5") (pin "1") (pinfunction "RF_OUT1_1") (pintype "output"))
    )
    (net (code "36") (name "Net-(IC5-RF_OUT2)") (class "Default")
      (node (ref "C20") (pin "2") (pinfunction "2_2") (pintype "passive"))
      (node (ref "IC5") (pin "3") (pinfunction "RF_OUT2_3") (pintype "output"))
    )
    (net (code "37") (name "Net-(J1-X)") (class "Default")
      (node (ref "C6") (pin "1") (pinfunction "1_1") (pintype "passive"))
      (node (ref "J1") (pin "1") (pinfunction "X_1") (pintype "passive"))
    )
    (net (code "38") (name "Net-(J2-X)") (class "Default")
      (node (ref "C9") (pin "1") (pinfunction "1_1") (pintype "passive"))
      (node (ref "J2") (pin "1") (pinfunction "X_1") (pintype "passive"))
    )
    (net (code "39") (name "Net-(J3-X)") (class "Default")
      (node (ref "C14") (pin "1") (pinfunction "1_1") (pintype "passive"))
      (node (ref "J3") (pin "1") (pinfunction "X_1") (pintype "passive"))
    )
    (net (code "40") (name "Net-(J4-X)") (class "Default")
      (node (ref "C20") (pin "1") (pinfunction "1_1") (pintype "passive"))
      (node (ref "J4") (pin "1") (pinfunction "X_1") (pintype "passive"))
    )
    (net (code "41") (name "Net-(J5-X)") (class "Default")
      (node (ref "C23") (pin "1") (pinfunction "1_1") (pintype "passive"))
      (node (ref "J5") (pin "1") (pinfunction "X_1") (pintype "passive"))
    )
    (net (code "42") (name "Net-(MN1-Pad1)") (class "Default")
      (node (ref "MN1") (pin "1") (pinfunction "1_1") (pintype "passive"))
      (node (ref "MN3") (pin "2") (pinfunction "2_2") (pintype "passive"))
    )
    (net (code "43") (name "Net-(MN2-Pad1)") (class "Default")
      (node (ref "MN2") (pin "1") (pinfunction "1_1") (pintype "passive"))
      (node (ref "MN4") (pin "2") (pinfunction "2_2") (pintype "passive"))
    )
    (net (code "44") (name "Net-(MN10-Pad1)") (class "Default")
      (node (ref "MN10") (pin "1") (pinfunction "1_1") (pintype "passive"))
      (node (ref "MN12") (pin "2") (pinfunction "2_2") (pintype "passive"))
    )
    (net (code "45") (name "Net-(MN11-Pad2)") (class "Default")
      (node (ref "MN11") (pin "2") (pinfunction "2_2") (pintype "passive"))
      (node (ref "MN9") (pin "1") (pinfunction "1_1") (pintype "passive"))
    )
    (net (code "46") (name "Net-(VT1-D)") (class "Default")
      (node (ref "RA1") (pin "2") (pinfunction "2_2") (pintype "passive"))
      (node (ref "VT1") (pin "2") (pinfunction "D_2") (pintype "passive"))
    )
    (net (code "47") (name "Net-(VT1-G1)") (class "Default")
      (node (ref "R14") (pin "1") (pinfunction "1_1") (pintype "passive"))
      (node (ref "VT1") (pin "3") (pinfunction "G2_3") (pintype "passive"))
      (node (ref "VT1") (pin "4") (pinfunction "G1_4") (pintype "passive"))
    )
    (net (code "48") (name "Net-(VT1-S)") (class "Default")
      (node (ref "C13") (pin "2") (pinfunction "2_2") (pintype "passive"))
      (node (ref "R15") (pin "1") (pinfunction "1_1") (pintype "passive"))
      (node (ref "RA2") (pin "1") (pinfunction "1_1") (pintype "passive"))
      (node (ref "RA3") (pin "2") (pinfunction "2_2") (pintype "passive"))
      (node (ref "VT1") (pin "1") (pinfunction "S_1") (pintype "passive"))
      (node (ref "VT3") (pin "2") (pinfunction "D_2") (pintype "passive"))
    )
    (net (code "49") (name "Net-(VT2-D)") (class "Default")
      (node (ref "C16") (pin "1") (pinfunction "1_1") (pintype "passive"))
      (node (ref "RA1") (pin "1") (pinfunction "1_1") (pintype "passive"))
      (node (ref "RA2") (pin "2") (pinfunction "2_2") (pintype "passive"))
      (node (ref "RA4") (pin "2") (pinfunction "2_2") (pintype "passive"))
      (node (ref "VT2") (pin "2") (pinfunction "D_2") (pintype "passive"))
    )
    (net (code "50") (name "Net-(VT2-G1)") (class "Default")
      (node (ref "R17") (pin "2") (pinfunction "2_2") (pintype "passive"))
      (node (ref "VT2") (pin "3") (pinfunction "G2_3") (pintype "passive"))
      (node (ref "VT2") (pin "4") (pinfunction "G1_4") (pintype "passive"))
    )
    (net (code "51") (name "Net-(VT3-G1)") (class "Default")
      (node (ref "R16") (pin "1") (pinfunction "1_1") (pintype "passive"))
      (node (ref "VT3") (pin "3") (pinfunction "G2_3") (pintype "passive"))
      (node (ref "VT3") (pin "4") (pinfunction "G1_4") (pintype "passive"))
    )
    (net (code "52") (name "VCC1P8_LMS") (class "Default")
      (node (ref "C4") (pin "2") (pinfunction "2_2") (pintype "passive"))
      (node (ref "C5") (pin "2") (pinfunction "2_2") (pintype "passive"))
      (node (ref "C7") (pin "2") (pinfunction "2_2") (pintype "passive"))
      (node (ref "C8") (pin "2") (pinfunction "2_2") (pintype "passive"))
      (node (ref "MN1") (pin "2") (pinfunction "2_2") (pintype "passive"))
      (node (ref "MN10") (pin "2") (pinfunction "2_2") (pintype "passive"))
      (node (ref "MN2") (pin "2") (pinfunction "2_2") (pintype "passive"))
      (node (ref "MN9") (pin "2") (pinfunction "2_2") (pintype "passive"))
      (node (ref "R15") (pin "2") (pinfunction "2_2") (pintype "passive"))
    )
  )
)
